# LM317.net
KiCad netlist of a schematic drawn in Altium Designer
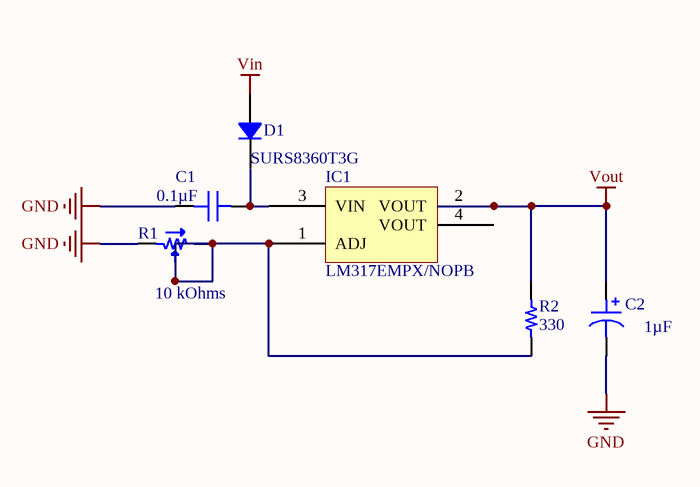
[diagram p0: LM317.SchDoc]

(export (version "E")
  (design (tool "Eeschema 10.0.6"))
  (components
    (comp (ref "C1")
      (value "0.1µF")
      (footprint "CAP 0805_2012")
      (description "CAP CER 0.1UF 50V X7R 0805")
      (fields (field (name "PART NUMBER") "CC0805MRX7R9BB104") (field (name "MANUFACTURER") "Yageo"))
      (libsource (lib "Celestial Altium Library - altium_library") (part "Capacitor"))
    )
    (comp (ref "C2")
      (value "1µF")
      (footprint "CAP ALSMD 4.3MM H5.4MM")
      (description "CAP ALUM 1UF 20% 50V SMD")
      (fields (field (name "PART NUMBER") "UZT1H010MCL1GB") (field (name "MANUFACTURER") "Nichicon"))
      (libsource (lib "Celestial Altium Library - altium_library") (part "Polarised Capacitor"))
    )
    (comp (ref "D1")
      (value "SURS8360T3G")
      (footprint "DO214AB SMC")
      (description "DIODE GEN PURP 600V 3A SMC")
      (fields (field (name "MANUFACTURER") "ON Semiconductor"))
      (libsource (lib "Celestial Altium Library - altium_library") (part "Diode"))
    )
    (comp (ref "IC1")
      (value "LM317EMPX/NOPB")
      (footprint "TI SOT-223 DCY")
      (description "IC REG LIN POS ADJ 1.5A SOT223-4")
      (fields (field (name "MANUFACTURER") "Texas Instruments"))
      (libsource (lib "Celestial Altium Library - altium_library") (part "TI LM317-N"))
    )
    (comp (ref "R1")
      (value "10 kOhms")
      (footprint "POT BOURNS TRIMPOT TC33")
      (description "TRIMMER 10K OHM 0.1W J LEAD TOP")
      (fields (field (name "PART NUMBER") "TC33X-2-103G") (field (name "MANUFACTURER") "Bourns Inc."))
      (libsource (lib "Celestial Altium Library - altium_library") (part "Potentiometer"))
    )
    (comp (ref "R2")
      (value "330")
      (footprint "RES 0805_2012")
      (description "RES 330 OHM 0.5% 1/8W 0805")
      (fields (field (name "PART NUMBER") "TNPW0805330RDEEA") (field (name "MANUFACTURER") "Vishay Dale"))
      (libsource (lib "Celestial Altium Library - altium_library") (part "Resistor"))
    )
  )
  (nets
    (net (code "1") (name "GND") (class "Default")
      (node (ref "C1") (pin "1") (pinfunction "1_1") (pintype "passive"))
      (node (ref "C2") (pin "2") (pinfunction "2_2") (pintype "passive"))
      (node (ref "R1") (pin "1") (pinfunction "1_1") (pintype "passive"))
    )
    (net (code "2") (name "Net-(IC1-ADJ)") (class "Default")
      (node (ref "IC1") (pin "1") (pinfunction "ADJ_1") (pintype "passive"))
      (node (ref "R1") (pin "2") (pinfunction "2_2") (pintype "passive"))
      (node (ref "R1") (pin "3") (pinfunction "3_3") (pintype "passive"))
      (node (ref "R2") (pin "1") (pinfunction "1_1") (pintype "passive"))
    )
    (net (code "3") (name "Net-(IC1-VIN)") (class "Default")
      (node (ref "C1") (pin "2") (pinfunction "2_2") (pintype "passive"))
      (node (ref "D1") (pin "2") (pinfunction "2_2") (pintype "passive"))
      (node (ref "IC1") (pin "3") (pinfunction "VIN_3") (pintype "passive"))
    )
    (net (code "4") (name "Vin") (class "Default")
      (node (ref "D1") (pin "1") (pinfunction "1_1") (pintype "passive"))
    )
    (net (code "5") (name "Vout") (class "Default")
      (node (ref "C2") (pin "1") (pinfunction "1_1") (pintype "passive"))
      (node (ref "IC1") (pin "2") (pinfunction "VOUT_2") (pintype "passive"))
      (node (ref "R2") (pin "2") (pinfunction "2_2") (pintype "passive"))
    )
    (net (code "6") (name "unconnected-(IC1-VOUT-Pad4)") (class "Default")
      (node (ref "IC1") (pin "4") (pinfunction "VOUT_4") (pintype "passive"))
    )
  )
)
